# NES_Controller.net
KiCad netlist of a schematic drawn in EAGLE
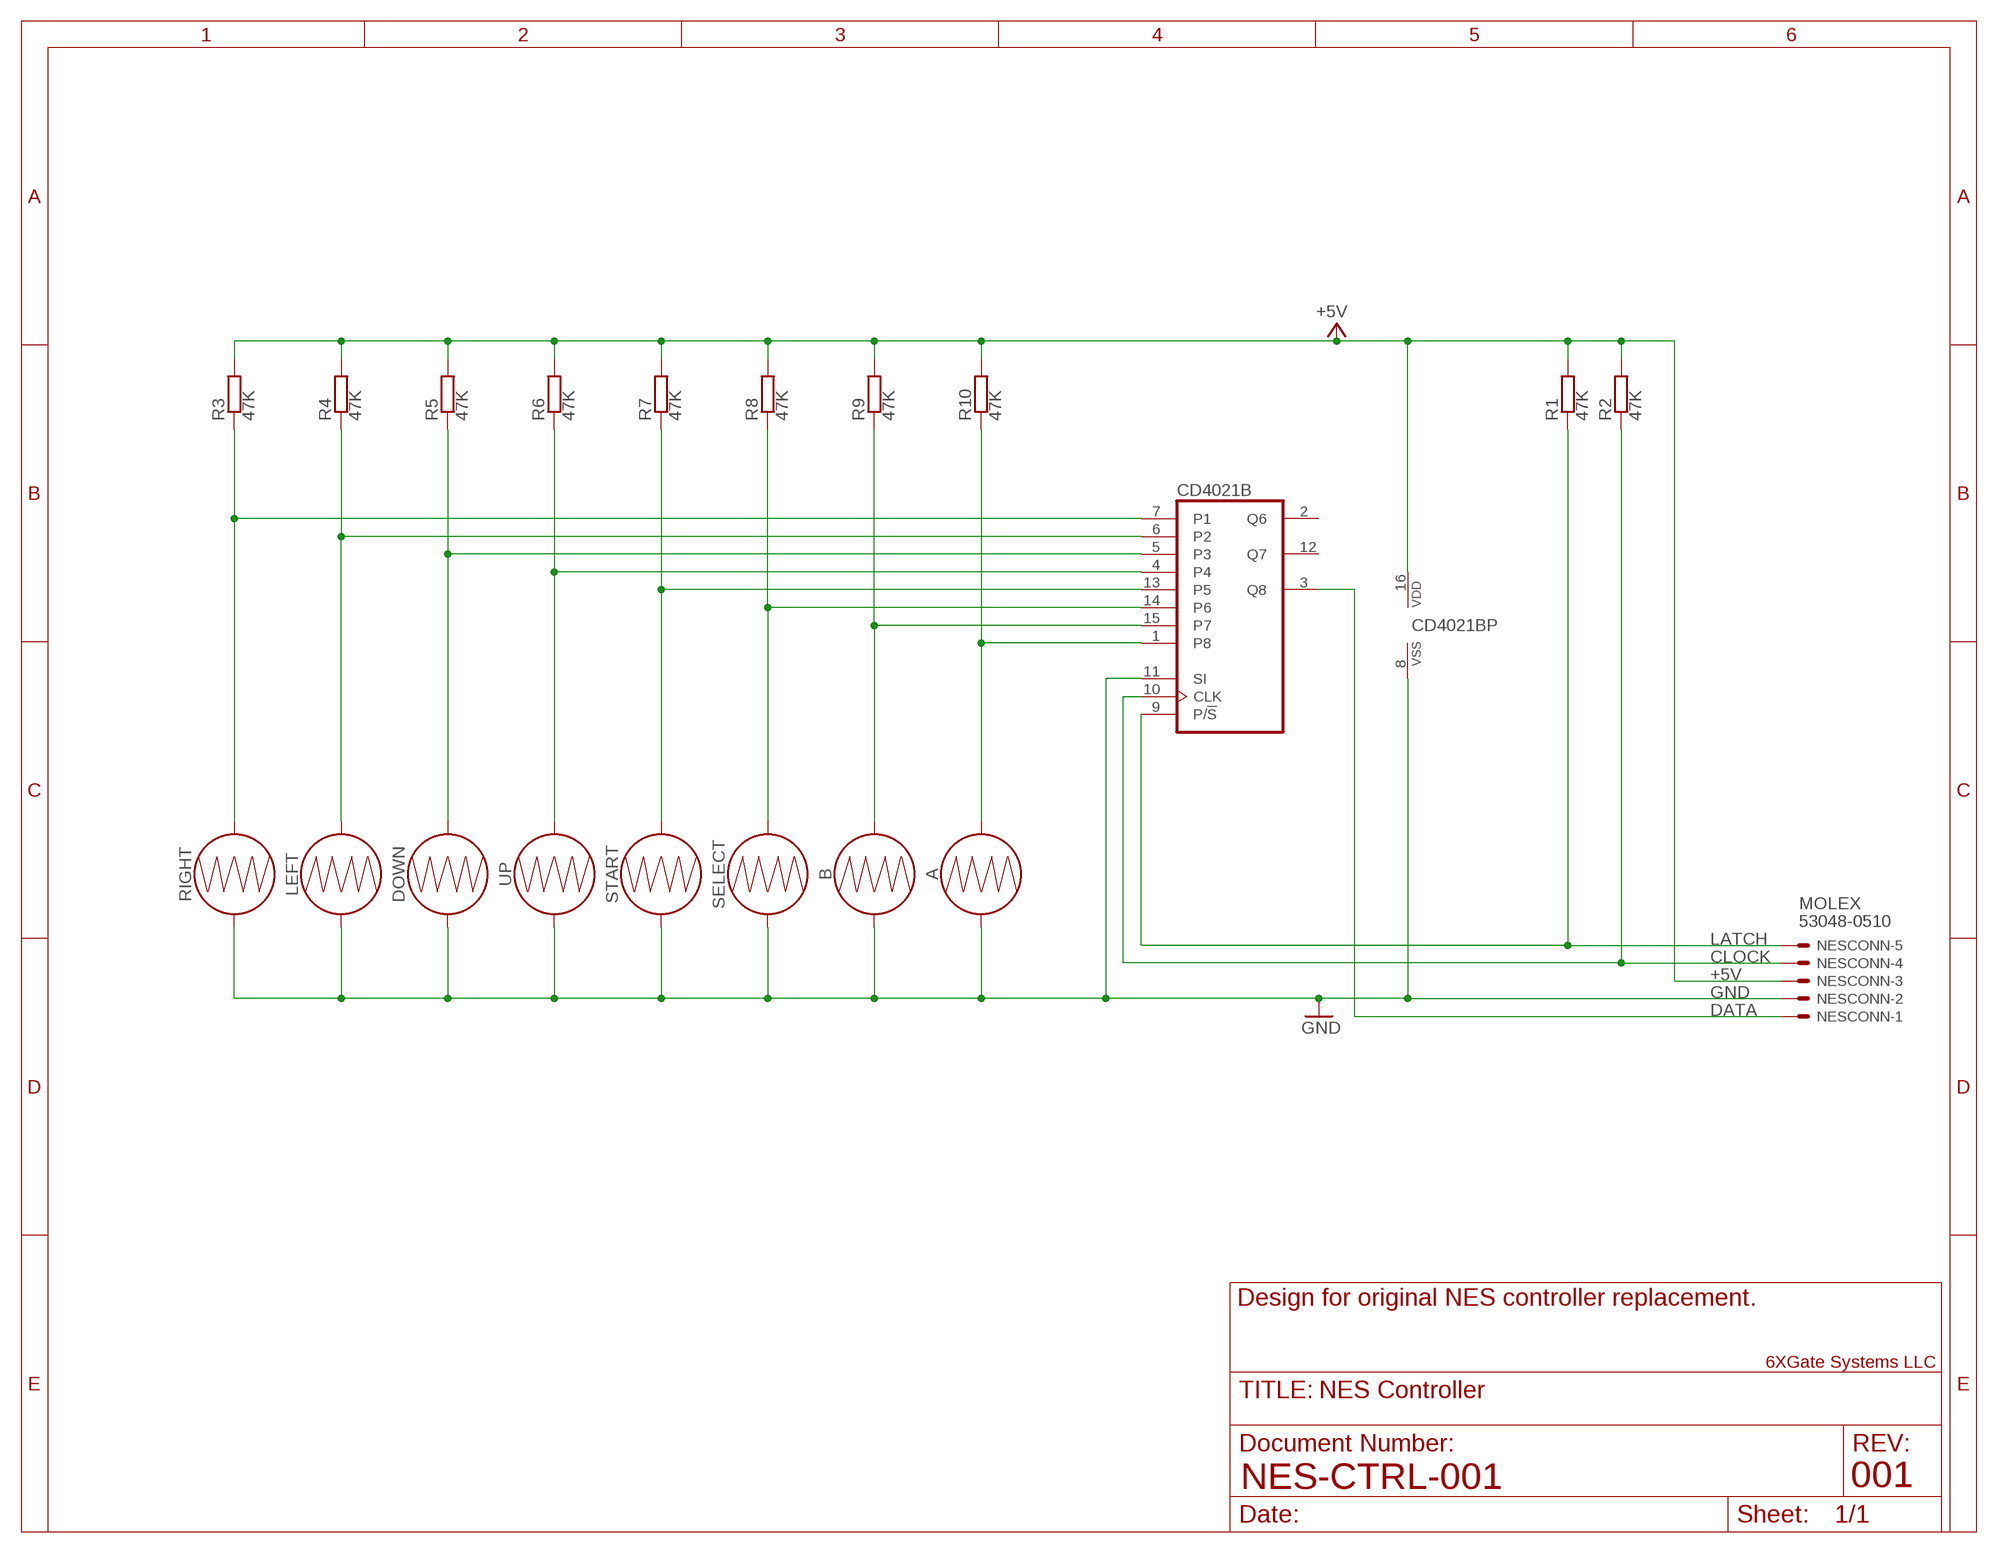
[diagram p0: schematic, sheet 1]

(export (version "E")
  (design (tool "Eeschema 10.0.6"))
  (components
    (comp (ref "A")
      (value "BUTTON-CONDUCTIVESMD")
      (footprint "eagle-import:BUTTON-CONDUCTIVE")
      (libsource (lib "eagle-import") (part "BUTTON-CONDUCTIVESMD"))
    )
    (comp (ref "B")
      (value "BUTTON-CONDUCTIVESMD")
      (footprint "eagle-import:BUTTON-CONDUCTIVE")
      (libsource (lib "eagle-import") (part "BUTTON-CONDUCTIVESMD"))
    )
    (comp (ref "CD4021B")
      (value "4021D")
      (footprint "eagle-import:SO16")
      (libsource (lib "eagle-import") (part "4021D"))
    )
    (comp (ref "DOWN")
      (value "BUTTON-CONDUCTIVESMD")
      (footprint "eagle-import:BUTTON-CONDUCTIVE")
      (libsource (lib "eagle-import") (part "BUTTON-CONDUCTIVESMD"))
    )
    (comp (ref "LEFT")
      (value "BUTTON-CONDUCTIVESMD")
      (footprint "eagle-import:BUTTON-CONDUCTIVE")
      (libsource (lib "eagle-import") (part "BUTTON-CONDUCTIVESMD"))
    )
    (comp (ref "NESCONN")
      (value "53048-05")
      (footprint "eagle-import:53048-05")
      (fields (field (name "MF") "MOLEX") (field (name "MPN") "53048-0510"))
      (libsource (lib "eagle-import") (part "53?-05048"))
    )
    (comp (ref "R1")
      (value "47K")
      (footprint "eagle-import:R0805")
      (libsource (lib "eagle-import") (part "R-EU_R0805"))
    )
    (comp (ref "R2")
      (value "47K")
      (footprint "eagle-import:R0805")
      (libsource (lib "eagle-import") (part "R-EU_R0805"))
    )
    (comp (ref "R3")
      (value "47K")
      (footprint "eagle-import:R0805")
      (libsource (lib "eagle-import") (part "R-EU_R0805"))
    )
    (comp (ref "R4")
      (value "47K")
      (footprint "eagle-import:R0805")
      (libsource (lib "eagle-import") (part "R-EU_R0805"))
    )
    (comp (ref "R5")
      (value "47K")
      (footprint "eagle-import:R0805")
      (libsource (lib "eagle-import") (part "R-EU_R0805"))
    )
    (comp (ref "R6")
      (value "47K")
      (footprint "eagle-import:R0805")
      (libsource (lib "eagle-import") (part "R-EU_R0805"))
    )
    (comp (ref "R7")
      (value "47K")
      (footprint "eagle-import:R0805")
      (libsource (lib "eagle-import") (part "R-EU_R0805"))
    )
    (comp (ref "R8")
      (value "47K")
      (footprint "eagle-import:R0805")
      (libsource (lib "eagle-import") (part "R-EU_R0805"))
    )
    (comp (ref "R9")
      (value "47K")
      (footprint "eagle-import:R0805")
      (libsource (lib "eagle-import") (part "R-EU_R0805"))
    )
    (comp (ref "R10")
      (value "47K")
      (footprint "eagle-import:R0805")
      (libsource (lib "eagle-import") (part "R-EU_R0805"))
    )
    (comp (ref "RIGHT")
      (value "BUTTON-CONDUCTIVESMD")
      (footprint "eagle-import:BUTTON-CONDUCTIVE")
      (libsource (lib "eagle-import") (part "BUTTON-CONDUCTIVESMD"))
    )
    (comp (ref "SELECT")
      (value "BUTTON-CONDUCTIVESMD")
      (footprint "eagle-import:BUTTON-CONDUCTIVE")
      (libsource (lib "eagle-import") (part "BUTTON-CONDUCTIVESMD"))
    )
    (comp (ref "START")
      (value "BUTTON-CONDUCTIVESMD")
      (footprint "eagle-import:BUTTON-CONDUCTIVE")
      (libsource (lib "eagle-import") (part "BUTTON-CONDUCTIVESMD"))
    )
    (comp (ref "UP")
      (value "BUTTON-CONDUCTIVESMD")
      (footprint "eagle-import:BUTTON-CONDUCTIVE")
      (libsource (lib "eagle-import") (part "BUTTON-CONDUCTIVESMD"))
    )
  )
  (nets
    (net (code "1") (name "+5V") (class "Default")
      (node (ref "CD4021B") (pin "16") (pinfunction "VDD_16") (pintype "power_in"))
      (node (ref "NESCONN") (pin "3") (pinfunction "S_3") (pintype "passive"))
      (node (ref "R1") (pin "2") (pinfunction "2_2") (pintype "passive"))
      (node (ref "R10") (pin "2") (pinfunction "2_2") (pintype "passive"))
      (node (ref "R2") (pin "2") (pinfunction "2_2") (pintype "passive"))
      (node (ref "R3") (pin "2") (pinfunction "2_2") (pintype "passive"))
      (node (ref "R4") (pin "2") (pinfunction "2_2") (pintype "passive"))
      (node (ref "R5") (pin "2") (pinfunction "2_2") (pintype "passive"))
      (node (ref "R6") (pin "2") (pinfunction "2_2") (pintype "passive"))
      (node (ref "R7") (pin "2") (pinfunction "2_2") (pintype "passive"))
      (node (ref "R8") (pin "2") (pinfunction "2_2") (pintype "passive"))
      (node (ref "R9") (pin "2") (pinfunction "2_2") (pintype "passive"))
    )
    (net (code "2") (name "/CLOCK") (class "Default")
      (node (ref "CD4021B") (pin "10") (pinfunction "CLK_10") (pintype "input"))
      (node (ref "NESCONN") (pin "4") (pinfunction "S_4") (pintype "passive"))
      (node (ref "R2") (pin "1") (pinfunction "1_1") (pintype "passive"))
    )
    (net (code "3") (name "/DATA") (class "Default")
      (node (ref "CD4021B") (pin "3") (pinfunction "Q8_3") (pintype "output"))
      (node (ref "NESCONN") (pin "1") (pinfunction "S_1") (pintype "passive"))
    )
    (net (code "4") (name "/LATCH") (class "Default")
      (node (ref "CD4021B") (pin "9") (pinfunction "P/~{S}_9") (pintype "input"))
      (node (ref "NESCONN") (pin "5") (pinfunction "S_5") (pintype "passive"))
      (node (ref "R1") (pin "1") (pinfunction "1_1") (pintype "passive"))
    )
    (net (code "5") (name "GND") (class "Default")
      (node (ref "A") (pin "2") (pinfunction "2_2") (pintype "passive"))
      (node (ref "B") (pin "2") (pinfunction "2_2") (pintype "passive"))
      (node (ref "CD4021B") (pin "11") (pinfunction "SI_11") (pintype "input"))
      (node (ref "CD4021B") (pin "8") (pinfunction "VSS_8") (pintype "power_in"))
      (node (ref "DOWN") (pin "1") (pinfunction "1_1") (pintype "passive"))
      (node (ref "LEFT") (pin "2") (pinfunction "2_2") (pintype "passive"))
      (node (ref "NESCONN") (pin "2") (pinfunction "S_2") (pintype "passive"))
      (node (ref "RIGHT") (pin "1") (pinfunction "1_1") (pintype "passive"))
      (node (ref "SELECT") (pin "2") (pinfunction "2_2") (pintype "passive"))
      (node (ref "START") (pin "1") (pinfunction "1_1") (pintype "passive"))
      (node (ref "UP") (pin "1") (pinfunction "1_1") (pintype "passive"))
    )
    (net (code "6") (name "Net-(CD4021BA-P1)") (class "Default")
      (node (ref "CD4021B") (pin "7") (pinfunction "P1_7") (pintype "input"))
      (node (ref "R3") (pin "1") (pinfunction "1_1") (pintype "passive"))
      (node (ref "RIGHT") (pin "2") (pinfunction "2_2") (pintype "passive"))
    )
    (net (code "7") (name "Net-(CD4021BA-P2)") (class "Default")
      (node (ref "CD4021B") (pin "6") (pinfunction "P2_6") (pintype "input"))
      (node (ref "LEFT") (pin "1") (pinfunction "1_1") (pintype "passive"))
      (node (ref "R4") (pin "1") (pinfunction "1_1") (pintype "passive"))
    )
    (net (code "8") (name "Net-(CD4021BA-P3)") (class "Default")
      (node (ref "CD4021B") (pin "5") (pinfunction "P3_5") (pintype "input"))
      (node (ref "DOWN") (pin "2") (pinfunction "2_2") (pintype "passive"))
      (node (ref "R5") (pin "1") (pinfunction "1_1") (pintype "passive"))
    )
    (net (code "9") (name "Net-(CD4021BA-P4)") (class "Default")
      (node (ref "CD4021B") (pin "4") (pinfunction "P4_4") (pintype "input"))
      (node (ref "R6") (pin "1") (pinfunction "1_1") (pintype "passive"))
      (node (ref "UP") (pin "2") (pinfunction "2_2") (pintype "passive"))
    )
    (net (code "10") (name "Net-(CD4021BA-P5)") (class "Default")
      (node (ref "CD4021B") (pin "13") (pinfunction "P5_13") (pintype "input"))
      (node (ref "R7") (pin "1") (pinfunction "1_1") (pintype "passive"))
      (node (ref "START") (pin "2") (pinfunction "2_2") (pintype "passive"))
    )
    (net (code "11") (name "Net-(CD4021BA-P6)") (class "Default")
      (node (ref "CD4021B") (pin "14") (pinfunction "P6_14") (pintype "input"))
      (node (ref "R8") (pin "1") (pinfunction "1_1") (pintype "passive"))
      (node (ref "SELECT") (pin "1") (pinfunction "1_1") (pintype "passive"))
    )
    (net (code "12") (name "Net-(CD4021BA-P7)") (class "Default")
      (node (ref "B") (pin "1") (pinfunction "1_1") (pintype "passive"))
      (node (ref "CD4021B") (pin "15") (pinfunction "P7_15") (pintype "input"))
      (node (ref "R9") (pin "1") (pinfunction "1_1") (pintype "passive"))
    )
    (net (code "13") (name "Net-(CD4021BA-P8)") (class "Default")
      (node (ref "A") (pin "1") (pinfunction "1_1") (pintype "passive"))
      (node (ref "CD4021B") (pin "1") (pinfunction "P8_1") (pintype "input"))
      (node (ref "R10") (pin "1") (pinfunction "1_1") (pintype "passive"))
    )
    (net (code "14") (name "unconnected-(CD4021BA-Q6-Pad2)") (class "Default")
      (node (ref "CD4021B") (pin "2") (pinfunction "Q6_2") (pintype "output"))
    )
    (net (code "15") (name "unconnected-(CD4021BA-Q7-Pad12)") (class "Default")
      (node (ref "CD4021B") (pin "12") (pinfunction "Q7_12") (pintype "output"))
    )
  )
)
